# display.net
KiCad netlist of a schematic drawn in EAGLE
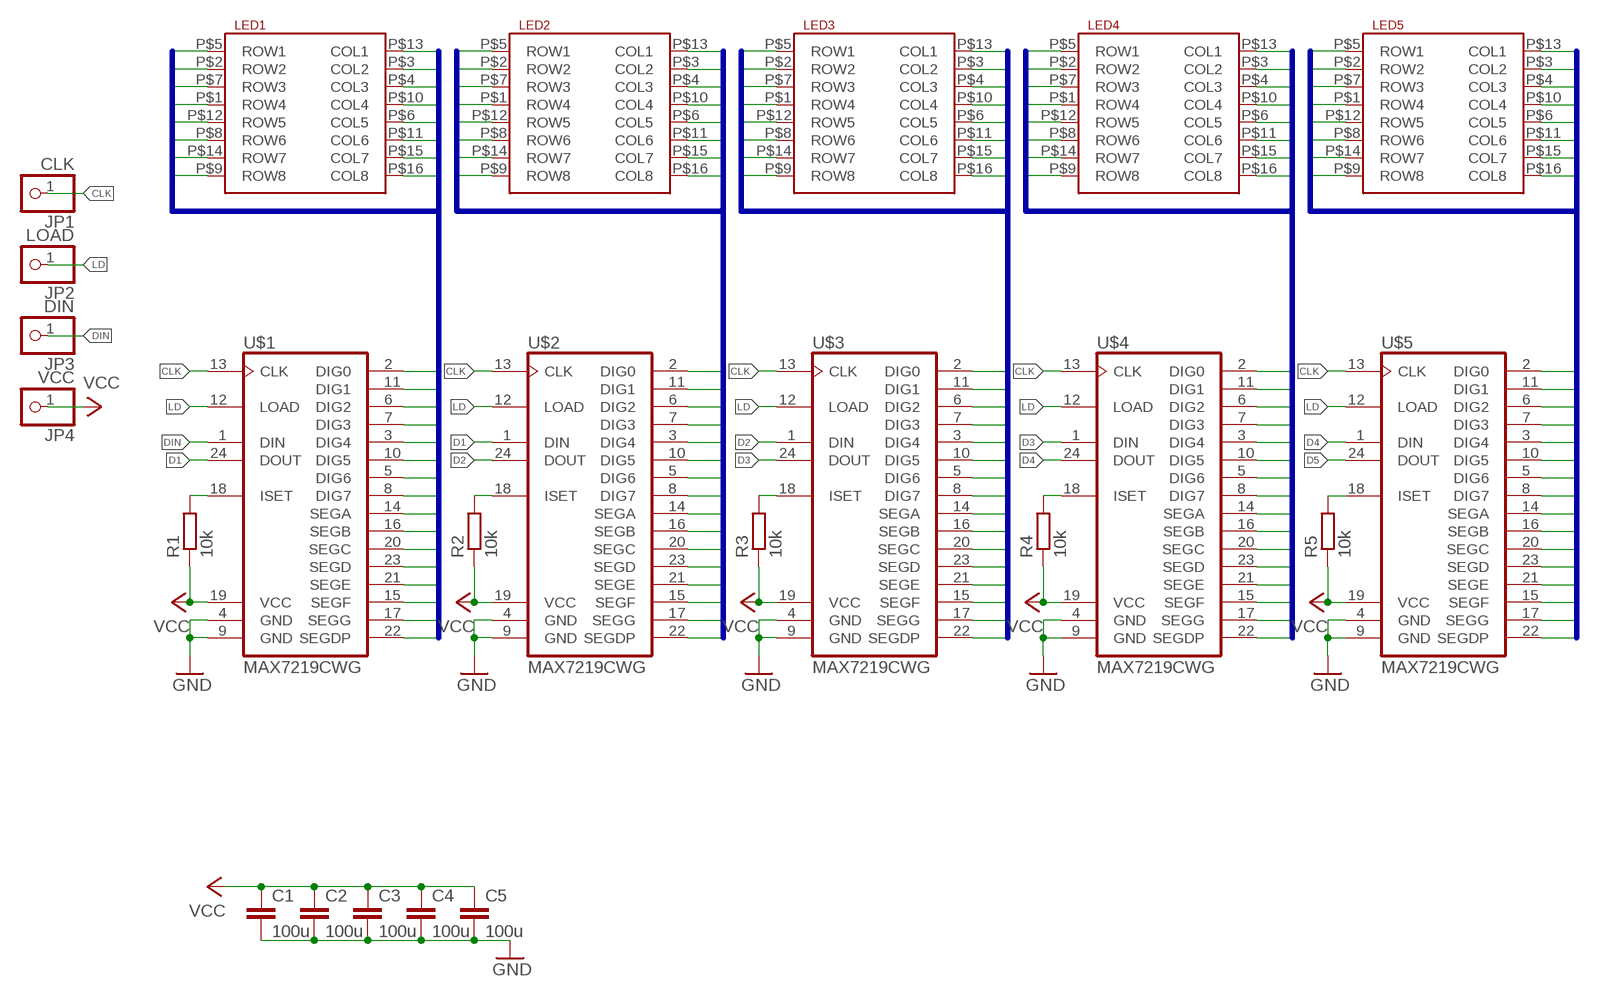
[diagram p0: schematic, sheet 1]

(export (version "E")
  (design (tool "Eeschema 10.0.6"))
  (components
    (comp (ref "C1")
      (value "100u")
      (footprint "eagle-import:C0805")
      (libsource (lib "eagle-import") (part "C-EUC0805"))
    )
    (comp (ref "C2")
      (value "100u")
      (footprint "eagle-import:C0805")
      (libsource (lib "eagle-import") (part "C-EUC0805"))
    )
    (comp (ref "C3")
      (value "100u")
      (footprint "eagle-import:C0805")
      (libsource (lib "eagle-import") (part "C-EUC0805"))
    )
    (comp (ref "C4")
      (value "100u")
      (footprint "eagle-import:C0805")
      (libsource (lib "eagle-import") (part "C-EUC0805"))
    )
    (comp (ref "C5")
      (value "100u")
      (footprint "eagle-import:C0805")
      (libsource (lib "eagle-import") (part "C-EUC0805"))
    )
    (comp (ref "JP1")
      (value "CLK")
      (footprint "eagle-import:1X01")
      (libsource (lib "eagle-import") (part "PINHD-1X1"))
    )
    (comp (ref "JP2")
      (value "LOAD")
      (footprint "eagle-import:1X01")
      (libsource (lib "eagle-import") (part "PINHD-1X1"))
    )
    (comp (ref "JP3")
      (value "DIN")
      (footprint "eagle-import:1X01")
      (libsource (lib "eagle-import") (part "PINHD-1X1"))
    )
    (comp (ref "JP4")
      (value "VCC")
      (footprint "eagle-import:1X01")
      (libsource (lib "eagle-import") (part "PINHD-1X1"))
    )
    (comp (ref "LED1")
      (value "LED_8X8_MATRIX07088BH")
      (footprint "eagle-import:MATRIX_8X8_20MM")
      (libsource (lib "eagle-import") (part "LED_8X8_MATRIX07088BH"))
    )
    (comp (ref "LED2")
      (value "LED_8X8_MATRIX07088BH")
      (footprint "eagle-import:MATRIX_8X8_20MM")
      (libsource (lib "eagle-import") (part "LED_8X8_MATRIX07088BH"))
    )
    (comp (ref "LED3")
      (value "LED_8X8_MATRIX07088BH")
      (footprint "eagle-import:MATRIX_8X8_20MM")
      (libsource (lib "eagle-import") (part "LED_8X8_MATRIX07088BH"))
    )
    (comp (ref "LED4")
      (value "LED_8X8_MATRIX07088BH")
      (footprint "eagle-import:MATRIX_8X8_20MM")
      (libsource (lib "eagle-import") (part "LED_8X8_MATRIX07088BH"))
    )
    (comp (ref "LED5")
      (value "LED_8X8_MATRIX07088BH")
      (footprint "eagle-import:MATRIX_8X8_20MM")
      (libsource (lib "eagle-import") (part "LED_8X8_MATRIX07088BH"))
    )
    (comp (ref "R1")
      (value "10k")
      (footprint "eagle-import:R0805")
      (libsource (lib "eagle-import") (part "R-EU_R0805"))
    )
    (comp (ref "R2")
      (value "10k")
      (footprint "eagle-import:R0805")
      (libsource (lib "eagle-import") (part "R-EU_R0805"))
    )
    (comp (ref "R3")
      (value "10k")
      (footprint "eagle-import:R0805")
      (libsource (lib "eagle-import") (part "R-EU_R0805"))
    )
    (comp (ref "R4")
      (value "10k")
      (footprint "eagle-import:R0805")
      (libsource (lib "eagle-import") (part "R-EU_R0805"))
    )
    (comp (ref "R5")
      (value "10k")
      (footprint "eagle-import:R0805")
      (libsource (lib "eagle-import") (part "R-EU_R0805"))
    )
    (comp (ref "U$1")
      (value "MAX7219CWG")
      (footprint "eagle-import:SO24L")
      (libsource (lib "eagle-import") (part "MAX7219CWG"))
    )
    (comp (ref "U$2")
      (value "MAX7219CWG")
      (footprint "eagle-import:SO24L")
      (libsource (lib "eagle-import") (part "MAX7219CWG"))
    )
    (comp (ref "U$3")
      (value "MAX7219CWG")
      (footprint "eagle-import:SO24L")
      (libsource (lib "eagle-import") (part "MAX7219CWG"))
    )
    (comp (ref "U$4")
      (value "MAX7219CWG")
      (footprint "eagle-import:SO24L")
      (libsource (lib "eagle-import") (part "MAX7219CWG"))
    )
    (comp (ref "U$5")
      (value "MAX7219CWG")
      (footprint "eagle-import:SO24L")
      (libsource (lib "eagle-import") (part "MAX7219CWG"))
    )
  )
  (nets
    (net (code "1") (name "/MATRIX1_ANODE1") (class "Default")
      (node (ref "LED1") (pin "P$5") (pinfunction "ROW1_P$5") (pintype "bidirectional"))
      (node (ref "U$1") (pin "14") (pinfunction "SEGA_14") (pintype "output"))
    )
    (net (code "2") (name "/MATRIX1_ANODE2") (class "Default")
      (node (ref "LED1") (pin "P$2") (pinfunction "ROW2_P$2") (pintype "bidirectional"))
      (node (ref "U$1") (pin "16") (pinfunction "SEGB_16") (pintype "output"))
    )
    (net (code "3") (name "/MATRIX1_ANODE3") (class "Default")
      (node (ref "LED1") (pin "P$7") (pinfunction "ROW3_P$7") (pintype "bidirectional"))
      (node (ref "U$1") (pin "20") (pinfunction "SEGC_20") (pintype "output"))
    )
    (net (code "4") (name "/MATRIX1_ANODE4") (class "Default")
      (node (ref "LED1") (pin "P$1") (pinfunction "ROW4_P$1") (pintype "bidirectional"))
      (node (ref "U$1") (pin "23") (pinfunction "SEGD_23") (pintype "output"))
    )
    (net (code "5") (name "/MATRIX1_ANODE5") (class "Default")
      (node (ref "LED1") (pin "P$12") (pinfunction "ROW5_P$12") (pintype "bidirectional"))
      (node (ref "U$1") (pin "21") (pinfunction "SEGE_21") (pintype "output"))
    )
    (net (code "6") (name "/MATRIX1_ANODE6") (class "Default")
      (node (ref "LED1") (pin "P$8") (pinfunction "ROW6_P$8") (pintype "bidirectional"))
      (node (ref "U$1") (pin "15") (pinfunction "SEGF_15") (pintype "output"))
    )
    (net (code "7") (name "/MATRIX1_ANODE7") (class "Default")
      (node (ref "LED1") (pin "P$14") (pinfunction "ROW7_P$14") (pintype "bidirectional"))
      (node (ref "U$1") (pin "17") (pinfunction "SEGG_17") (pintype "output"))
    )
    (net (code "8") (name "/MATRIX1_ANODE8") (class "Default")
      (node (ref "LED1") (pin "P$9") (pinfunction "ROW8_P$9") (pintype "bidirectional"))
      (node (ref "U$1") (pin "22") (pinfunction "SEGDP_22") (pintype "output"))
    )
    (net (code "9") (name "/MATRIX1_CATHODE1") (class "Default")
      (node (ref "LED1") (pin "P$13") (pinfunction "COL1_P$13") (pintype "bidirectional"))
      (node (ref "U$1") (pin "2") (pinfunction "DIG0_2") (pintype "output"))
    )
    (net (code "10") (name "/MATRIX1_CATHODE2") (class "Default")
      (node (ref "LED1") (pin "P$3") (pinfunction "COL2_P$3") (pintype "bidirectional"))
      (node (ref "U$1") (pin "11") (pinfunction "DIG1_11") (pintype "output"))
    )
    (net (code "11") (name "/MATRIX1_CATHODE3") (class "Default")
      (node (ref "LED1") (pin "P$4") (pinfunction "COL3_P$4") (pintype "bidirectional"))
      (node (ref "U$1") (pin "6") (pinfunction "DIG2_6") (pintype "output"))
    )
    (net (code "12") (name "/MATRIX1_CATHODE4") (class "Default")
      (node (ref "LED1") (pin "P$10") (pinfunction "COL4_P$10") (pintype "bidirectional"))
      (node (ref "U$1") (pin "7") (pinfunction "DIG3_7") (pintype "output"))
    )
    (net (code "13") (name "/MATRIX1_CATHODE5") (class "Default")
      (node (ref "LED1") (pin "P$6") (pinfunction "COL5_P$6") (pintype "bidirectional"))
      (node (ref "U$1") (pin "3") (pinfunction "DIG4_3") (pintype "output"))
    )
    (net (code "14") (name "/MATRIX1_CATHODE6") (class "Default")
      (node (ref "LED1") (pin "P$11") (pinfunction "COL6_P$11") (pintype "bidirectional"))
      (node (ref "U$1") (pin "10") (pinfunction "DIG5_10") (pintype "output"))
    )
    (net (code "15") (name "/MATRIX1_CATHODE7") (class "Default")
      (node (ref "LED1") (pin "P$15") (pinfunction "COL7_P$15") (pintype "bidirectional"))
      (node (ref "U$1") (pin "5") (pinfunction "DIG6_5") (pintype "output"))
    )
    (net (code "16") (name "/MATRIX1_CATHODE8") (class "Default")
      (node (ref "LED1") (pin "P$16") (pinfunction "COL8_P$16") (pintype "bidirectional"))
      (node (ref "U$1") (pin "8") (pinfunction "DIG7_8") (pintype "output"))
    )
    (net (code "17") (name "/MATRIX2_ANODE1") (class "Default")
      (node (ref "LED2") (pin "P$5") (pinfunction "ROW1_P$5") (pintype "bidirectional"))
      (node (ref "U$2") (pin "14") (pinfunction "SEGA_14") (pintype "output"))
    )
    (net (code "18") (name "/MATRIX2_ANODE2") (class "Default")
      (node (ref "LED2") (pin "P$2") (pinfunction "ROW2_P$2") (pintype "bidirectional"))
      (node (ref "U$2") (pin "16") (pinfunction "SEGB_16") (pintype "output"))
    )
    (net (code "19") (name "/MATRIX2_ANODE3") (class "Default")
      (node (ref "LED2") (pin "P$7") (pinfunction "ROW3_P$7") (pintype "bidirectional"))
      (node (ref "U$2") (pin "20") (pinfunction "SEGC_20") (pintype "output"))
    )
    (net (code "20") (name "/MATRIX2_ANODE4") (class "Default")
      (node (ref "LED2") (pin "P$1") (pinfunction "ROW4_P$1") (pintype "bidirectional"))
      (node (ref "U$2") (pin "23") (pinfunction "SEGD_23") (pintype "output"))
    )
    (net (code "21") (name "/MATRIX2_ANODE5") (class "Default")
      (node (ref "LED2") (pin "P$12") (pinfunction "ROW5_P$12") (pintype "bidirectional"))
      (node (ref "U$2") (pin "21") (pinfunction "SEGE_21") (pintype "output"))
    )
    (net (code "22") (name "/MATRIX2_ANODE6") (class "Default")
      (node (ref "LED2") (pin "P$8") (pinfunction "ROW6_P$8") (pintype "bidirectional"))
      (node (ref "U$2") (pin "15") (pinfunction "SEGF_15") (pintype "output"))
    )
    (net (code "23") (name "/MATRIX2_ANODE7") (class "Default")
      (node (ref "LED2") (pin "P$14") (pinfunction "ROW7_P$14") (pintype "bidirectional"))
      (node (ref "U$2") (pin "17") (pinfunction "SEGG_17") (pintype "output"))
    )
    (net (code "24") (name "/MATRIX2_ANODE8") (class "Default")
      (node (ref "LED2") (pin "P$9") (pinfunction "ROW8_P$9") (pintype "bidirectional"))
      (node (ref "U$2") (pin "22") (pinfunction "SEGDP_22") (pintype "output"))
    )
    (net (code "25") (name "/MATRIX2_CATHODE1") (class "Default")
      (node (ref "LED2") (pin "P$13") (pinfunction "COL1_P$13") (pintype "bidirectional"))
      (node (ref "U$2") (pin "2") (pinfunction "DIG0_2") (pintype "output"))
    )
    (net (code "26") (name "/MATRIX2_CATHODE2") (class "Default")
      (node (ref "LED2") (pin "P$3") (pinfunction "COL2_P$3") (pintype "bidirectional"))
      (node (ref "U$2") (pin "11") (pinfunction "DIG1_11") (pintype "output"))
    )
    (net (code "27") (name "/MATRIX2_CATHODE3") (class "Default")
      (node (ref "LED2") (pin "P$4") (pinfunction "COL3_P$4") (pintype "bidirectional"))
      (node (ref "U$2") (pin "6") (pinfunction "DIG2_6") (pintype "output"))
    )
    (net (code "28") (name "/MATRIX2_CATHODE4") (class "Default")
      (node (ref "LED2") (pin "P$10") (pinfunction "COL4_P$10") (pintype "bidirectional"))
      (node (ref "U$2") (pin "7") (pinfunction "DIG3_7") (pintype "output"))
    )
    (net (code "29") (name "/MATRIX2_CATHODE5") (class "Default")
      (node (ref "LED2") (pin "P$6") (pinfunction "COL5_P$6") (pintype "bidirectional"))
      (node (ref "U$2") (pin "3") (pinfunction "DIG4_3") (pintype "output"))
    )
    (net (code "30") (name "/MATRIX2_CATHODE6") (class "Default")
      (node (ref "LED2") (pin "P$11") (pinfunction "COL6_P$11") (pintype "bidirectional"))
      (node (ref "U$2") (pin "10") (pinfunction "DIG5_10") (pintype "output"))
    )
    (net (code "31") (name "/MATRIX2_CATHODE7") (class "Default")
      (node (ref "LED2") (pin "P$15") (pinfunction "COL7_P$15") (pintype "bidirectional"))
      (node (ref "U$2") (pin "5") (pinfunction "DIG6_5") (pintype "output"))
    )
    (net (code "32") (name "/MATRIX2_CATHODE8") (class "Default")
      (node (ref "LED2") (pin "P$16") (pinfunction "COL8_P$16") (pintype "bidirectional"))
      (node (ref "U$2") (pin "8") (pinfunction "DIG7_8") (pintype "output"))
    )
    (net (code "33") (name "/MATRIX3_ANODE1") (class "Default")
      (node (ref "LED3") (pin "P$5") (pinfunction "ROW1_P$5") (pintype "bidirectional"))
      (node (ref "U$3") (pin "14") (pinfunction "SEGA_14") (pintype "output"))
    )
    (net (code "34") (name "/MATRIX3_ANODE2") (class "Default")
      (node (ref "LED3") (pin "P$2") (pinfunction "ROW2_P$2") (pintype "bidirectional"))
      (node (ref "U$3") (pin "16") (pinfunction "SEGB_16") (pintype "output"))
    )
    (net (code "35") (name "/MATRIX3_ANODE3") (class "Default")
      (node (ref "LED3") (pin "P$7") (pinfunction "ROW3_P$7") (pintype "bidirectional"))
      (node (ref "U$3") (pin "20") (pinfunction "SEGC_20") (pintype "output"))
    )
    (net (code "36") (name "/MATRIX3_ANODE4") (class "Default")
      (node (ref "LED3") (pin "P$1") (pinfunction "ROW4_P$1") (pintype "bidirectional"))
      (node (ref "U$3") (pin "23") (pinfunction "SEGD_23") (pintype "output"))
    )
    (net (code "37") (name "/MATRIX3_ANODE5") (class "Default")
      (node (ref "LED3") (pin "P$12") (pinfunction "ROW5_P$12") (pintype "bidirectional"))
      (node (ref "U$3") (pin "21") (pinfunction "SEGE_21") (pintype "output"))
    )
    (net (code "38") (name "/MATRIX3_ANODE6") (class "Default")
      (node (ref "LED3") (pin "P$8") (pinfunction "ROW6_P$8") (pintype "bidirectional"))
      (node (ref "U$3") (pin "15") (pinfunction "SEGF_15") (pintype "output"))
    )
    (net (code "39") (name "/MATRIX3_ANODE7") (class "Default")
      (node (ref "LED3") (pin "P$14") (pinfunction "ROW7_P$14") (pintype "bidirectional"))
      (node (ref "U$3") (pin "17") (pinfunction "SEGG_17") (pintype "output"))
    )
    (net (code "40") (name "/MATRIX3_ANODE8") (class "Default")
      (node (ref "LED3") (pin "P$9") (pinfunction "ROW8_P$9") (pintype "bidirectional"))
      (node (ref "U$3") (pin "22") (pinfunction "SEGDP_22") (pintype "output"))
    )
    (net (code "41") (name "/MATRIX3_CATHODE1") (class "Default")
      (node (ref "LED3") (pin "P$13") (pinfunction "COL1_P$13") (pintype "bidirectional"))
      (node (ref "U$3") (pin "2") (pinfunction "DIG0_2") (pintype "output"))
    )
    (net (code "42") (name "/MATRIX3_CATHODE2") (class "Default")
      (node (ref "LED3") (pin "P$3") (pinfunction "COL2_P$3") (pintype "bidirectional"))
      (node (ref "U$3") (pin "11") (pinfunction "DIG1_11") (pintype "output"))
    )
    (net (code "43") (name "/MATRIX3_CATHODE3") (class "Default")
      (node (ref "LED3") (pin "P$4") (pinfunction "COL3_P$4") (pintype "bidirectional"))
      (node (ref "U$3") (pin "6") (pinfunction "DIG2_6") (pintype "output"))
    )
    (net (code "44") (name "/MATRIX3_CATHODE4") (class "Default")
      (node (ref "LED3") (pin "P$10") (pinfunction "COL4_P$10") (pintype "bidirectional"))
      (node (ref "U$3") (pin "7") (pinfunction "DIG3_7") (pintype "output"))
    )
    (net (code "45") (name "/MATRIX3_CATHODE5") (class "Default")
      (node (ref "LED3") (pin "P$6") (pinfunction "COL5_P$6") (pintype "bidirectional"))
      (node (ref "U$3") (pin "3") (pinfunction "DIG4_3") (pintype "output"))
    )
    (net (code "46") (name "/MATRIX3_CATHODE6") (class "Default")
      (node (ref "LED3") (pin "P$11") (pinfunction "COL6_P$11") (pintype "bidirectional"))
      (node (ref "U$3") (pin "10") (pinfunction "DIG5_10") (pintype "output"))
    )
    (net (code "47") (name "/MATRIX3_CATHODE7") (class "Default")
      (node (ref "LED3") (pin "P$15") (pinfunction "COL7_P$15") (pintype "bidirectional"))
      (node (ref "U$3") (pin "5") (pinfunction "DIG6_5") (pintype "output"))
    )
    (net (code "48") (name "/MATRIX3_CATHODE8") (class "Default")
      (node (ref "LED3") (pin "P$16") (pinfunction "COL8_P$16") (pintype "bidirectional"))
      (node (ref "U$3") (pin "8") (pinfunction "DIG7_8") (pintype "output"))
    )
    (net (code "49") (name "/MATRIX4_ANODE1") (class "Default")
      (node (ref "LED4") (pin "P$5") (pinfunction "ROW1_P$5") (pintype "bidirectional"))
      (node (ref "U$4") (pin "14") (pinfunction "SEGA_14") (pintype "output"))
    )
    (net (code "50") (name "/MATRIX4_ANODE2") (class "Default")
      (node (ref "LED4") (pin "P$2") (pinfunction "ROW2_P$2") (pintype "bidirectional"))
      (node (ref "U$4") (pin "16") (pinfunction "SEGB_16") (pintype "output"))
    )
    (net (code "51") (name "/MATRIX4_ANODE3") (class "Default")
      (node (ref "LED4") (pin "P$7") (pinfunction "ROW3_P$7") (pintype "bidirectional"))
      (node (ref "U$4") (pin "20") (pinfunction "SEGC_20") (pintype "output"))
    )
    (net (code "52") (name "/MATRIX4_ANODE4") (class "Default")
      (node (ref "LED4") (pin "P$1") (pinfunction "ROW4_P$1") (pintype "bidirectional"))
      (node (ref "U$4") (pin "23") (pinfunction "SEGD_23") (pintype "output"))
    )
    (net (code "53") (name "/MATRIX4_ANODE5") (class "Default")
      (node (ref "LED4") (pin "P$12") (pinfunction "ROW5_P$12") (pintype "bidirectional"))
      (node (ref "U$4") (pin "21") (pinfunction "SEGE_21") (pintype "output"))
    )
    (net (code "54") (name "/MATRIX4_ANODE6") (class "Default")
      (node (ref "LED4") (pin "P$8") (pinfunction "ROW6_P$8") (pintype "bidirectional"))
      (node (ref "U$4") (pin "15") (pinfunction "SEGF_15") (pintype "output"))
    )
    (net (code "55") (name "/MATRIX4_ANODE7") (class "Default")
      (node (ref "LED4") (pin "P$14") (pinfunction "ROW7_P$14") (pintype "bidirectional"))
      (node (ref "U$4") (pin "17") (pinfunction "SEGG_17") (pintype "output"))
    )
    (net (code "56") (name "/MATRIX4_ANODE8") (class "Default")
      (node (ref "LED4") (pin "P$9") (pinfunction "ROW8_P$9") (pintype "bidirectional"))
      (node (ref "U$4") (pin "22") (pinfunction "SEGDP_22") (pintype "output"))
    )
    (net (code "57") (name "/MATRIX4_CATHODE1") (class "Default")
      (node (ref "LED4") (pin "P$13") (pinfunction "COL1_P$13") (pintype "bidirectional"))
      (node (ref "U$4") (pin "2") (pinfunction "DIG0_2") (pintype "output"))
    )
    (net (code "58") (name "/MATRIX4_CATHODE2") (class "Default")
      (node (ref "LED4") (pin "P$3") (pinfunction "COL2_P$3") (pintype "bidirectional"))
      (node (ref "U$4") (pin "11") (pinfunction "DIG1_11") (pintype "output"))
    )
    (net (code "59") (name "/MATRIX4_CATHODE3") (class "Default")
      (node (ref "LED4") (pin "P$4") (pinfunction "COL3_P$4") (pintype "bidirectional"))
      (node (ref "U$4") (pin "6") (pinfunction "DIG2_6") (pintype "output"))
    )
    (net (code "60") (name "/MATRIX4_CATHODE4") (class "Default")
      (node (ref "LED4") (pin "P$10") (pinfunction "COL4_P$10") (pintype "bidirectional"))
      (node (ref "U$4") (pin "7") (pinfunction "DIG3_7") (pintype "output"))
    )
    (net (code "61") (name "/MATRIX4_CATHODE5") (class "Default")
      (node (ref "LED4") (pin "P$6") (pinfunction "COL5_P$6") (pintype "bidirectional"))
      (node (ref "U$4") (pin "3") (pinfunction "DIG4_3") (pintype "output"))
    )
    (net (code "62") (name "/MATRIX4_CATHODE6") (class "Default")
      (node (ref "LED4") (pin "P$11") (pinfunction "COL6_P$11") (pintype "bidirectional"))
      (node (ref "U$4") (pin "10") (pinfunction "DIG5_10") (pintype "output"))
    )
    (net (code "63") (name "/MATRIX4_CATHODE7") (class "Default")
      (node (ref "LED4") (pin "P$15") (pinfunction "COL7_P$15") (pintype "bidirectional"))
      (node (ref "U$4") (pin "5") (pinfunction "DIG6_5") (pintype "output"))
    )
    (net (code "64") (name "/MATRIX4_CATHODE8") (class "Default")
      (node (ref "LED4") (pin "P$16") (pinfunction "COL8_P$16") (pintype "bidirectional"))
      (node (ref "U$4") (pin "8") (pinfunction "DIG7_8") (pintype "output"))
    )
    (net (code "65") (name "/MATRIX5_ANODE1") (class "Default")
      (node (ref "LED5") (pin "P$5") (pinfunction "ROW1_P$5") (pintype "bidirectional"))
      (node (ref "U$5") (pin "14") (pinfunction "SEGA_14") (pintype "output"))
    )
    (net (code "66") (name "/MATRIX5_ANODE2") (class "Default")
      (node (ref "LED5") (pin "P$2") (pinfunction "ROW2_P$2") (pintype "bidirectional"))
      (node (ref "U$5") (pin "16") (pinfunction "SEGB_16") (pintype "output"))
    )
    (net (code "67") (name "/MATRIX5_ANODE3") (class "Default")
      (node (ref "LED5") (pin "P$7") (pinfunction "ROW3_P$7") (pintype "bidirectional"))
      (node (ref "U$5") (pin "20") (pinfunction "SEGC_20") (pintype "output"))
    )
    (net (code "68") (name "/MATRIX5_ANODE4") (class "Default")
      (node (ref "LED5") (pin "P$1") (pinfunction "ROW4_P$1") (pintype "bidirectional"))
      (node (ref "U$5") (pin "23") (pinfunction "SEGD_23") (pintype "output"))
    )
    (net (code "69") (name "/MATRIX5_ANODE5") (class "Default")
      (node (ref "LED5") (pin "P$12") (pinfunction "ROW5_P$12") (pintype "bidirectional"))
      (node (ref "U$5") (pin "21") (pinfunction "SEGE_21") (pintype "output"))
    )
    (net (code "70") (name "/MATRIX5_ANODE6") (class "Default")
      (node (ref "LED5") (pin "P$8") (pinfunction "ROW6_P$8") (pintype "bidirectional"))
      (node (ref "U$5") (pin "15") (pinfunction "SEGF_15") (pintype "output"))
    )
    (net (code "71") (name "/MATRIX5_ANODE7") (class "Default")
      (node (ref "LED5") (pin "P$14") (pinfunction "ROW7_P$14") (pintype "bidirectional"))
      (node (ref "U$5") (pin "17") (pinfunction "SEGG_17") (pintype "output"))
    )
    (net (code "72") (name "/MATRIX5_ANODE8") (class "Default")
      (node (ref "LED5") (pin "P$9") (pinfunction "ROW8_P$9") (pintype "bidirectional"))
      (node (ref "U$5") (pin "22") (pinfunction "SEGDP_22") (pintype "output"))
    )
    (net (code "73") (name "/MATRIX5_CATHODE1") (class "Default")
      (node (ref "LED5") (pin "P$13") (pinfunction "COL1_P$13") (pintype "bidirectional"))
      (node (ref "U$5") (pin "2") (pinfunction "DIG0_2") (pintype "output"))
    )
    (net (code "74") (name "/MATRIX5_CATHODE2") (class "Default")
      (node (ref "LED5") (pin "P$3") (pinfunction "COL2_P$3") (pintype "bidirectional"))
      (node (ref "U$5") (pin "11") (pinfunction "DIG1_11") (pintype "output"))
    )
    (net (code "75") (name "/MATRIX5_CATHODE3") (class "Default")
      (node (ref "LED5") (pin "P$4") (pinfunction "COL3_P$4") (pintype "bidirectional"))
      (node (ref "U$5") (pin "6") (pinfunction "DIG2_6") (pintype "output"))
    )
    (net (code "76") (name "/MATRIX5_CATHODE4") (class "Default")
      (node (ref "LED5") (pin "P$10") (pinfunction "COL4_P$10") (pintype "bidirectional"))
      (node (ref "U$5") (pin "7") (pinfunction "DIG3_7") (pintype "output"))
    )
    (net (code "77") (name "/MATRIX5_CATHODE5") (class "Default")
      (node (ref "LED5") (pin "P$6") (pinfunction "COL5_P$6") (pintype "bidirectional"))
      (node (ref "U$5") (pin "3") (pinfunction "DIG4_3") (pintype "output"))
    )
    (net (code "78") (name "/MATRIX5_CATHODE6") (class "Default")
      (node (ref "LED5") (pin "P$11") (pinfunction "COL6_P$11") (pintype "bidirectional"))
      (node (ref "U$5") (pin "10") (pinfunction "DIG5_10") (pintype "output"))
    )
    (net (code "79") (name "/MATRIX5_CATHODE7") (class "Default")
      (node (ref "LED5") (pin "P$15") (pinfunction "COL7_P$15") (pintype "bidirectional"))
      (node (ref "U$5") (pin "5") (pinfunction "DIG6_5") (pintype "output"))
    )
    (net (code "80") (name "/MATRIX5_CATHODE8") (class "Default")
      (node (ref "LED5") (pin "P$16") (pinfunction "COL8_P$16") (pintype "bidirectional"))
      (node (ref "U$5") (pin "8") (pinfunction "DIG7_8") (pintype "output"))
    )
    (net (code "81") (name "CLK") (class "Default")
      (node (ref "JP1") (pin "1") (pinfunction "1_1") (pintype "passive"))
      (node (ref "U$1") (pin "13") (pinfunction "CLK_13") (pintype "input"))
      (node (ref "U$2") (pin "13") (pinfunction "CLK_13") (pintype "input"))
      (node (ref "U$3") (pin "13") (pinfunction "CLK_13") (pintype "input"))
      (node (ref "U$4") (pin "13") (pinfunction "CLK_13") (pintype "input"))
      (node (ref "U$5") (pin "13") (pinfunction "CLK_13") (pintype "input"))
    )
    (net (code "82") (name "D1") (class "Default")
      (node (ref "U$1") (pin "24") (pinfunction "DOUT_24") (pintype "output"))
      (node (ref "U$2") (pin "1") (pinfunction "DIN_1") (pintype "input"))
    )
    (net (code "83") (name "D2") (class "Default")
      (node (ref "U$2") (pin "24") (pinfunction "DOUT_24") (pintype "output"))
      (node (ref "U$3") (pin "1") (pinfunction "DIN_1") (pintype "input"))
    )
    (net (code "84") (name "D3") (class "Default")
      (node (ref "U$3") (pin "24") (pinfunction "DOUT_24") (pintype "output"))
      (node (ref "U$4") (pin "1") (pinfunction "DIN_1") (pintype "input"))
    )
    (net (code "85") (name "D4") (class "Default")
      (node (ref "U$4") (pin "24") (pinfunction "DOUT_24") (pintype "output"))
      (node (ref "U$5") (pin "1") (pinfunction "DIN_1") (pintype "input"))
    )
    (net (code "86") (name "D5") (class "Default")
      (node (ref "U$5") (pin "24") (pinfunction "DOUT_24") (pintype "output"))
    )
    (net (code "87") (name "DIN") (class "Default")
      (node (ref "JP3") (pin "1") (pinfunction "1_1") (pintype "passive"))
      (node (ref "U$1") (pin "1") (pinfunction "DIN_1") (pintype "input"))
    )
    (net (code "88") (name "GND") (class "Default")
      (node (ref "C1") (pin "2") (pinfunction "2_2") (pintype "passive"))
      (node (ref "C2") (pin "2") (pinfunction "2_2") (pintype "passive"))
      (node (ref "C3") (pin "2") (pinfunction "2_2") (pintype "passive"))
      (node (ref "C4") (pin "2") (pinfunction "2_2") (pintype "passive"))
      (node (ref "C5") (pin "2") (pinfunction "2_2") (pintype "passive"))
      (node (ref "U$1") (pin "4") (pinfunction "GND_4") (pintype "power_in"))
      (node (ref "U$1") (pin "9") (pinfunction "GND_9") (pintype "power_in"))
      (node (ref "U$2") (pin "4") (pinfunction "GND_4") (pintype "power_in"))
      (node (ref "U$2") (pin "9") (pinfunction "GND_9") (pintype "power_in"))
      (node (ref "U$3") (pin "4") (pinfunction "GND_4") (pintype "power_in"))
      (node (ref "U$3") (pin "9") (pinfunction "GND_9") (pintype "power_in"))
      (node (ref "U$4") (pin "4") (pinfunction "GND_4") (pintype "power_in"))
      (node (ref "U$4") (pin "9") (pinfunction "GND_9") (pintype "power_in"))
      (node (ref "U$5") (pin "4") (pinfunction "GND_4") (pintype "power_in"))
      (node (ref "U$5") (pin "9") (pinfunction "GND_9") (pintype "power_in"))
    )
    (net (code "89") (name "LD") (class "Default")
      (node (ref "JP2") (pin "1") (pinfunction "1_1") (pintype "passive"))
      (node (ref "U$1") (pin "12") (pinfunction "LOAD_12") (pintype "input"))
      (node (ref "U$2") (pin "12") (pinfunction "LOAD_12") (pintype "input"))
      (node (ref "U$3") (pin "12") (pinfunction "LOAD_12") (pintype "input"))
      (node (ref "U$4") (pin "12") (pinfunction "LOAD_12") (pintype "input"))
      (node (ref "U$5") (pin "12") (pinfunction "LOAD_12") (pintype "input"))
    )
    (net (code "90") (name "Net-(U$1-ISET)") (class "Default")
      (node (ref "R1") (pin "2") (pinfunction "2_2") (pintype "passive"))
      (node (ref "U$1") (pin "18") (pinfunction "ISET_18") (pintype "input"))
    )
    (net (code "91") (name "Net-(U$2-ISET)") (class "Default")
      (node (ref "R2") (pin "2") (pinfunction "2_2") (pintype "passive"))
      (node (ref "U$2") (pin "18") (pinfunction "ISET_18") (pintype "input"))
    )
    (net (code "92") (name "Net-(U$3-ISET)") (class "Default")
      (node (ref "R3") (pin "2") (pinfunction "2_2") (pintype "passive"))
      (node (ref "U$3") (pin "18") (pinfunction "ISET_18") (pintype "input"))
    )
    (net (code "93") (name "Net-(U$4-ISET)") (class "Default")
      (node (ref "R4") (pin "2") (pinfunction "2_2") (pintype "passive"))
      (node (ref "U$4") (pin "18") (pinfunction "ISET_18") (pintype "input"))
    )
    (net (code "94") (name "Net-(U$5-ISET)") (class "Default")
      (node (ref "R5") (pin "2") (pinfunction "2_2") (pintype "passive"))
      (node (ref "U$5") (pin "18") (pinfunction "ISET_18") (pintype "input"))
    )
    (net (code "95") (name "VCC") (class "Default")
      (node (ref "C1") (pin "1") (pinfunction "1_1") (pintype "passive"))
      (node (ref "C2") (pin "1") (pinfunction "1_1") (pintype "passive"))
      (node (ref "C3") (pin "1") (pinfunction "1_1") (pintype "passive"))
      (node (ref "C4") (pin "1") (pinfunction "1_1") (pintype "passive"))
      (node (ref "C5") (pin "1") (pinfunction "1_1") (pintype "passive"))
      (node (ref "JP4") (pin "1") (pinfunction "1_1") (pintype "passive"))
      (node (ref "R1") (pin "1") (pinfunction "1_1") (pintype "passive"))
      (node (ref "R2") (pin "1") (pinfunction "1_1") (pintype "passive"))
      (node (ref "R3") (pin "1") (pinfunction "1_1") (pintype "passive"))
      (node (ref "R4") (pin "1") (pinfunction "1_1") (pintype "passive"))
      (node (ref "R5") (pin "1") (pinfunction "1_1") (pintype "passive"))
      (node (ref "U$1") (pin "19") (pinfunction "VCC_19") (pintype "power_in"))
      (node (ref "U$2") (pin "19") (pinfunction "VCC_19") (pintype "power_in"))
      (node (ref "U$3") (pin "19") (pinfunction "VCC_19") (pintype "power_in"))
      (node (ref "U$4") (pin "19") (pinfunction "VCC_19") (pintype "power_in"))
      (node (ref "U$5") (pin "19") (pinfunction "VCC_19") (pintype "power_in"))
    )
  )
)
